# Controller-Sheet.net
KiCad netlist of a schematic drawn in Altium Designer
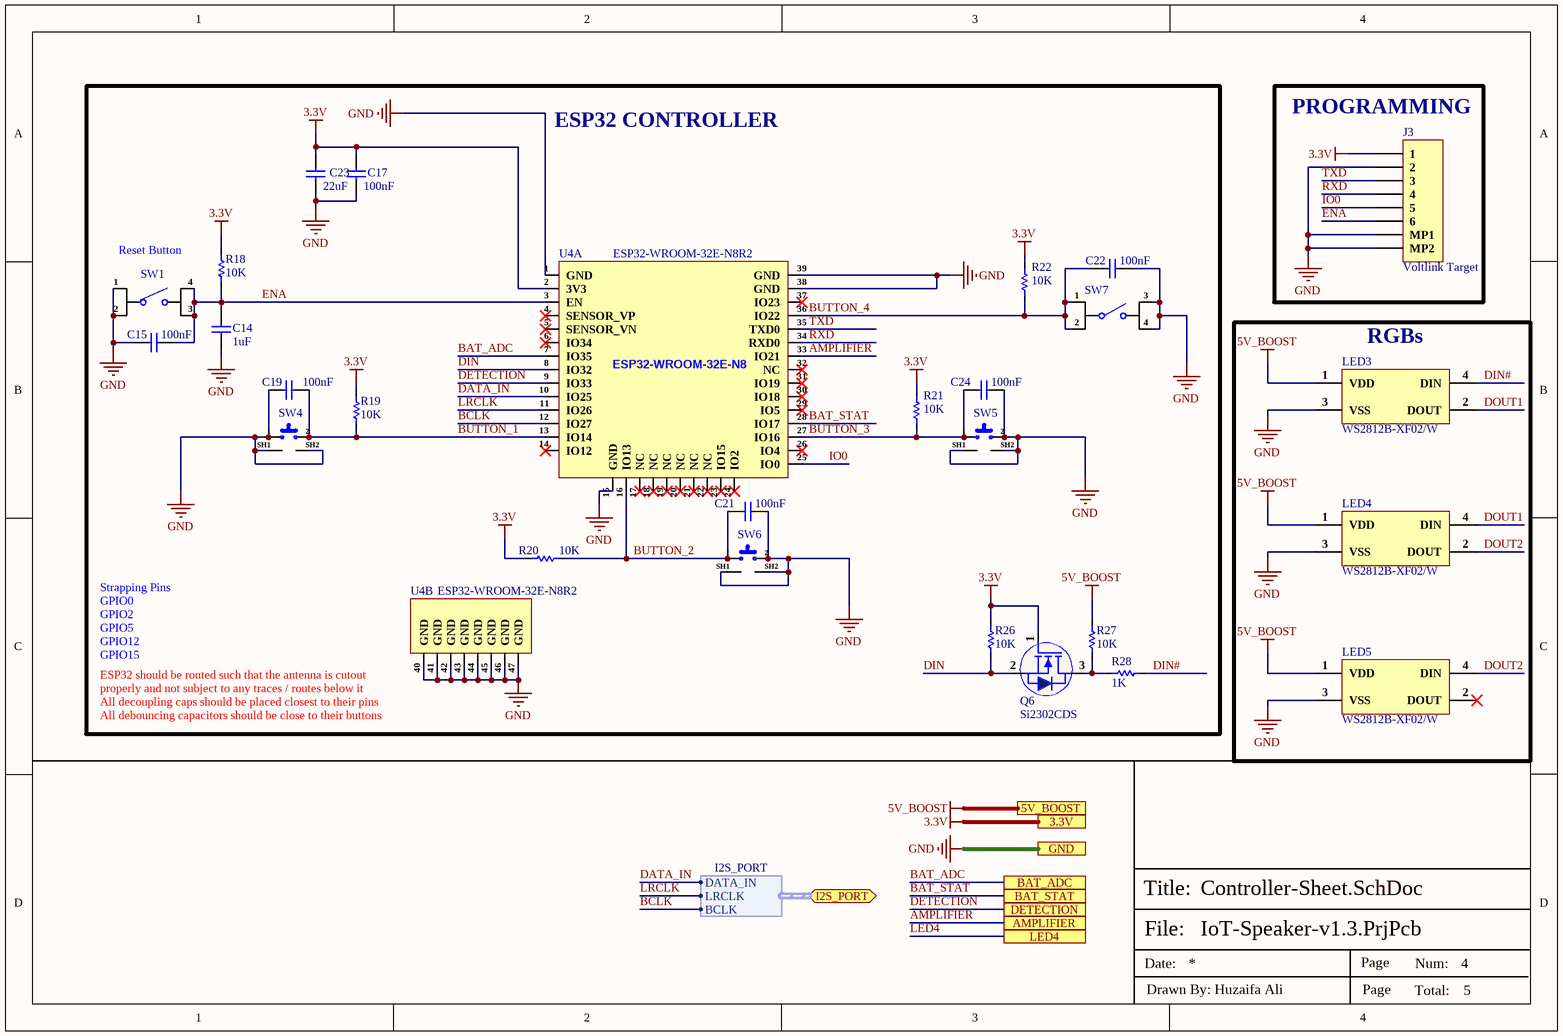
[diagram p0: Controller-Sheet.SchDoc]

(export (version "E")
  (design (tool "Eeschema 10.0.6"))
  (components
    (comp (ref "C14")
      (value "1uF")
      (footprint "Cap-0603")
      (description "CAP CER 1UF 25V X5R 0603")
      (fields
        (field (name "MANUFACTURER") "Yageo")
        (field (name "MANUFACTURER PART NUMBER") "CC0603KRX5R8BB105")
      )
      (libsource (lib "eSpark_centralized_Library(2022)") (part "CC0603KRX5R8BB105"))
    )
    (comp (ref "C15")
      (value "100nF")
      (footprint "Cap-0402")
      (description "CAP CER 0.1UF 25V X5R 0402")
      (fields
        (field (name "MANUFACTURER") "Yageo")
        (field (name "MANUFACTURER PART NUMBER") "CC0402KRX5R8BB104")
      )
      (libsource (lib "eSpark_centralized_Library(2022)") (part "CC0402KRX5R8BB104"))
    )
    (comp (ref "C17")
      (value "100nF")
      (footprint "Cap-0402")
      (description "CAP CER 0.1UF 25V X5R 0402")
      (fields
        (field (name "MANUFACTURER") "Yageo")
        (field (name "MANUFACTURER PART NUMBER") "CC0402KRX5R8BB104")
      )
      (libsource (lib "eSpark_centralized_Library(2022)") (part "CC0402KRX5R8BB104"))
    )
    (comp (ref "C19")
      (value "100nF")
      (footprint "Cap-0402")
      (description "CAP CER 0.1UF 25V X5R 0402")
      (fields
        (field (name "MANUFACTURER") "Yageo")
        (field (name "MANUFACTURER PART NUMBER") "CC0402KRX5R8BB104")
      )
      (libsource (lib "eSpark_centralized_Library(2022)") (part "CC0402KRX5R8BB104"))
    )
    (comp (ref "C21")
      (value "100nF")
      (footprint "Cap-0402")
      (description "CAP CER 0.1UF 25V X5R 0402")
      (fields
        (field (name "MANUFACTURER") "Yageo")
        (field (name "MANUFACTURER PART NUMBER") "CC0402KRX5R8BB104")
      )
      (libsource (lib "eSpark_centralized_Library(2022)") (part "CC0402KRX5R8BB104"))
    )
    (comp (ref "C22")
      (value "100nF")
      (footprint "Cap-0402")
      (description "CAP CER 0.1UF 25V X5R 0402")
      (fields
        (field (name "MANUFACTURER") "Yageo")
        (field (name "MANUFACTURER PART NUMBER") "CC0402KRX5R8BB104")
      )
      (libsource (lib "eSpark_centralized_Library(2022)") (part "CC0402KRX5R8BB104"))
    )
    (comp (ref "C23")
      (value "22uF")
      (footprint "Cap-0603")
      (description "CAP CER 22UF 10V X5R 0603")
      (fields
        (field (name "MANUFACTURER") "Yageo")
        (field (name "MANUFACTURER PART NUMBER") "CC0603MRX5R6BB226")
      )
      (libsource (lib "eSpark_centralized_Library(2022)") (part "CC0603MRX5R6BB226"))
    )
    (comp (ref "C24")
      (value "100nF")
      (footprint "Cap-0402")
      (description "CAP CER 0.1UF 25V X5R 0402")
      (fields
        (field (name "MANUFACTURER") "Yageo")
        (field (name "MANUFACTURER PART NUMBER") "CC0402KRX5R8BB104")
      )
      (libsource (lib "eSpark_centralized_Library(2022)") (part "CC0402KRX5R8BB104"))
    )
    (comp (ref "J3")
      (value "Voltlink Target")
      (footprint "Voltlink Target")
      (description "1x6P SH 1 1mm 6 SMD,P=1mm Wire To Board / Wire To Wire Connector ROHS")
      (fields (field (name "MANUFACTURER") "BOOMELE") (field (name "MANUFACTURER PART NUMBER") "C145963"))
      (libsource (lib "eSpark_centralized_Library(2022)") (part "C145963"))
    )
    (comp (ref "LED3")
      (value "WS2812B-XF02/W")
      (footprint "WS2812B-XF02/W")
      (description "SMD5050 Light Emitting Diodes (LED) ROHS")
      (fields (field (name "MANUFACTURER") "Worldsemi") (field (name "LCSC PART NUMBER") "C4154882"))
      (libsource (lib "eSpark_centralized_Library(2022)") (part "WS2812B-XF02/W"))
    )
    (comp (ref "LED4")
      (value "WS2812B-XF02/W")
      (footprint "WS2812B-XF02/W")
      (description "SMD5050 Light Emitting Diodes (LED) ROHS")
      (fields (field (name "MANUFACTURER") "Worldsemi") (field (name "LCSC PART NUMBER") "C4154882"))
      (libsource (lib "eSpark_centralized_Library(2022)") (part "WS2812B-XF02/W"))
    )
    (comp (ref "LED5")
      (value "WS2812B-XF02/W")
      (footprint "WS2812B-XF02/W")
      (description "SMD5050 Light Emitting Diodes (LED) ROHS")
      (fields (field (name "MANUFACTURER") "Worldsemi") (field (name "LCSC PART NUMBER") "C4154882"))
      (libsource (lib "eSpark_centralized_Library(2022)") (part "WS2812B-XF02/W"))
    )
    (comp (ref "Q6")
      (value "Si2302CDS")
      (footprint "Sot-23")
      (description "N-CHANNEL 20-V (D-S) MOSFET")
      (fields
        (field (name "MANUFACTURER") "TECH PUBLIC")
        (field (name "MANUFACTURER PART NUMBER") "SI2302CDS")
      )
      (libsource (lib "eSpark_centralized_Library(2022)") (part "Si2302CDS"))
    )
    (comp (ref "R18")
      (value "10K")
      (footprint "Res-0603")
      (description "RES SMD 10K Ohm 1% 1/10W 0603")
      (fields
        (field (name "MANUFACTURER") "Yageo")
        (field (name "MANUFACTURER PART NUMBER") "RC0603FR-0710KL")
      )
      (libsource (lib "eSpark_centralized_Library(2022)") (part "RC0603FR-0710KL"))
    )
    (comp (ref "R19")
      (value "10K")
      (footprint "Res-0603")
      (description "RES SMD 10K Ohm 1% 1/10W 0603")
      (fields
        (field (name "MANUFACTURER") "Yageo")
        (field (name "MANUFACTURER PART NUMBER") "RC0603FR-0710KL")
      )
      (libsource (lib "eSpark_centralized_Library(2022)") (part "RC0603FR-0710KL"))
    )
    (comp (ref "R20")
      (value "10K")
      (footprint "Res-0603")
      (description "RES SMD 10K Ohm 1% 1/10W 0603")
      (fields
        (field (name "MANUFACTURER") "Yageo")
        (field (name "MANUFACTURER PART NUMBER") "RC0603FR-0710KL")
      )
      (libsource (lib "eSpark_centralized_Library(2022)") (part "RC0603FR-0710KL"))
    )
    (comp (ref "R21")
      (value "10K")
      (footprint "Res-0603")
      (description "RES SMD 10K Ohm 1% 1/10W 0603")
      (fields
        (field (name "MANUFACTURER") "Yageo")
        (field (name "MANUFACTURER PART NUMBER") "RC0603FR-0710KL")
      )
      (libsource (lib "eSpark_centralized_Library(2022)") (part "RC0603FR-0710KL"))
    )
    (comp (ref "R22")
      (value "10K")
      (footprint "Res-0603")
      (description "RES SMD 10K Ohm 1% 1/10W 0603")
      (fields
        (field (name "MANUFACTURER") "Yageo")
        (field (name "MANUFACTURER PART NUMBER") "RC0603FR-0710KL")
      )
      (libsource (lib "eSpark_centralized_Library(2022)") (part "RC0603FR-0710KL"))
    )
    (comp (ref "R26")
      (value "10K")
      (footprint "Res-0402")
      (description "RES 10K OHM 1% 1/16W 0402")
      (fields
        (field (name "MANUFACTURER") "Yageo")
        (field (name "MANUFACTURER PART NUMBER") "RC0402FR-0710KL")
      )
      (libsource (lib "eSpark_centralized_Library(2022)") (part "RC0402FR-0710KL"))
    )
    (comp (ref "R27")
      (value "10K")
      (footprint "Res-0402")
      (description "RES 10K OHM 1% 1/16W 0402")
      (fields
        (field (name "MANUFACTURER") "Yageo")
        (field (name "MANUFACTURER PART NUMBER") "RC0402FR-0710KL")
      )
      (libsource (lib "eSpark_centralized_Library(2022)") (part "RC0402FR-0710KL"))
    )
    (comp (ref "R28")
      (value "1K")
      (footprint "Res-0603")
      (description "RES SMD 1K OHM 1% 1/10W 0603")
      (fields
        (field (name "MANUFACTURER") "Yageo")
        (field (name "MANUFACTURER PART NUMBER") "RC0603FR-071KL")
      )
      (libsource (lib "eSpark_centralized_Library(2022)") (part "RC0603FR-071KL"))
    )
    (comp (ref "SW1")
      (value "TS-1109S-C-B")
      (footprint "TS-1109S-C-B")
      (fields (field (name "MANUFACTURER") "XKB Connectivity") (field (name "LCSC PART NUMBER") "C381037"))
      (libsource (lib "eSpark_centralized_Library(2022)") (part "TS-1109S-C-B"))
    )
    (comp (ref "SW4")
      (value "TS-1087E-B3D2")
      (footprint "TS-1087E-B3D2")
      (description "Plugin-4P,7.7x3.5mm Tactile Switches ROHS")
      (fields (field (name "MANUFACTURER") "Yuandi") (field (name "LCSC PART NUMBER") "C541963"))
      (libsource (lib "eSpark Libraries") (part "TS-1087E-B3D2"))
    )
    (comp (ref "SW5")
      (value "TS-1087E-B3D2")
      (footprint "TS-1087E-B3D2")
      (description "Plugin-4P,7.7x3.5mm Tactile Switches ROHS")
      (fields (field (name "MANUFACTURER") "Yuandi") (field (name "LCSC PART NUMBER") "C541963"))
      (libsource (lib "eSpark Libraries") (part "TS-1087E-B3D2"))
    )
    (comp (ref "SW6")
      (value "TS-1087E-B3D2")
      (footprint "TS-1087E-B3D2")
      (description "Plugin-4P,7.7x3.5mm Tactile Switches ROHS")
      (fields (field (name "MANUFACTURER") "Yuandi") (field (name "LCSC PART NUMBER") "C541963"))
      (libsource (lib "eSpark Libraries") (part "TS-1087E-B3D2"))
    )
    (comp (ref "SW7")
      (value "TS-1109S-B-J")
      (footprint "TS-1109S-B-J_")
      (fields (field (name "MANUFACTURER") "XKB Connectivity") (field (name "LCSC PART NUMBER") "C480323"))
      (libsource (lib "eSpark_centralized_Library(2022)") (part "TS-1109S-B-J"))
    )
    (comp (ref "U4")
      (value "ESP32-WROOM-32E-N8R2")
      (footprint "38-SMD Module")
      (description "RF TXRX MODULE BT PCB TRACE SMD")
      (fields (field (name "MANUFACTURER") "Espressif Systems") (field (name "LCSC PART NUMBER") "C5361945"))
      (libsource (lib "eSpark Libraries") (part "ESP32-WROOM-32E-N8R2"))
    )
  )
  (nets
    (net (code "2") (name "/AMPLIFIER") (class "Default")
      (node (ref "U4") (pin "33") (pinfunction "IO21_33") (pintype "passive"))
    )
    (net (code "3") (name "/BAT_ADC") (class "Default")
      (node (ref "U4") (pin "7") (pinfunction "IO35_7") (pintype "passive"))
    )
    (net (code "4") (name "/BAT_STAT") (class "Default")
      (node (ref "U4") (pin "28") (pinfunction "IO17_28") (pintype "passive"))
    )
    (net (code "5") (name "/BCLK") (class "Default")
      (node (ref "U4") (pin "12") (pinfunction "IO27_12") (pintype "passive"))
    )
    (net (code "6") (name "/BUTTON_1") (class "Default")
      (node (ref "C19") (pin "1") (pinfunction "1_1") (pintype "passive"))
      (node (ref "R19") (pin "1") (pinfunction "1_1") (pintype "passive"))
      (node (ref "SW4") (pin "2") (pinfunction "2_2") (pintype "passive"))
      (node (ref "U4") (pin "13") (pinfunction "IO14_13") (pintype "passive"))
    )
    (net (code "7") (name "/BUTTON_2") (class "Default")
      (node (ref "C21") (pin "1") (pinfunction "1_1") (pintype "passive"))
      (node (ref "R20") (pin "1") (pinfunction "1_1") (pintype "passive"))
      (node (ref "SW6") (pin "1") (pinfunction "1_1") (pintype "passive"))
      (node (ref "U4") (pin "16") (pinfunction "IO13_16") (pintype "passive"))
    )
    (net (code "8") (name "/BUTTON_3") (class "Default")
      (node (ref "C24") (pin "1") (pinfunction "1_1") (pintype "passive"))
      (node (ref "R21") (pin "1") (pinfunction "1_1") (pintype "passive"))
      (node (ref "SW5") (pin "1") (pinfunction "1_1") (pintype "passive"))
      (node (ref "U4") (pin "27") (pinfunction "IO16_27") (pintype "passive"))
    )
    (net (code "9") (name "/BUTTON_4") (class "Default")
      (node (ref "C22") (pin "1") (pinfunction "1_1") (pintype "passive"))
      (node (ref "R22") (pin "1") (pinfunction "1_1") (pintype "passive"))
      (node (ref "SW7") (pin "1") (pinfunction "1_1") (pintype "passive"))
      (node (ref "SW7") (pin "2") (pinfunction "2_2") (pintype "passive"))
      (node (ref "U4") (pin "36") (pinfunction "IO22_36") (pintype "passive"))
    )
    (net (code "10") (name "/DATA_IN") (class "Default")
      (node (ref "U4") (pin "10") (pinfunction "IO25_10") (pintype "passive"))
    )
    (net (code "11") (name "/DETECTION") (class "Default")
      (node (ref "U4") (pin "9") (pinfunction "IO33_9") (pintype "passive"))
    )
    (net (code "12") (name "/DIN") (class "Default")
      (node (ref "Q6") (pin "2") (pinfunction "S_2") (pintype "passive"))
      (node (ref "R26") (pin "2") (pinfunction "2_2") (pintype "passive"))
      (node (ref "U4") (pin "8") (pinfunction "IO32_8") (pintype "passive"))
    )
    (net (code "13") (name "/DIN#") (class "Default")
      (node (ref "LED3") (pin "4") (pinfunction "DIN_4") (pintype "passive"))
      (node (ref "R28") (pin "2") (pinfunction "2_2") (pintype "passive"))
    )
    (net (code "14") (name "/DOUT1") (class "Default")
      (node (ref "LED3") (pin "2") (pinfunction "DOUT_2") (pintype "passive"))
      (node (ref "LED4") (pin "4") (pinfunction "DIN_4") (pintype "passive"))
    )
    (net (code "15") (name "/DOUT2") (class "Default")
      (node (ref "LED4") (pin "2") (pinfunction "DOUT_2") (pintype "passive"))
      (node (ref "LED5") (pin "4") (pinfunction "DIN_4") (pintype "passive"))
    )
    (net (code "16") (name "/ENA") (class "Default")
      (node (ref "C14") (pin "2") (pinfunction "2_2") (pintype "passive"))
      (node (ref "C15") (pin "2") (pinfunction "2_2") (pintype "passive"))
      (node (ref "J3") (pin "6") (pinfunction "6_6") (pintype "passive"))
      (node (ref "R18") (pin "1") (pinfunction "1_1") (pintype "passive"))
      (node (ref "SW1") (pin "3") (pinfunction "3_3") (pintype "passive"))
      (node (ref "SW1") (pin "4") (pinfunction "4_4") (pintype "passive"))
      (node (ref "U4") (pin "3") (pinfunction "EN_3") (pintype "passive"))
    )
    (net (code "17") (name "/IO0") (class "Default")
      (node (ref "J3") (pin "5") (pinfunction "5_5") (pintype "passive"))
      (node (ref "U4") (pin "25") (pinfunction "IO0_25") (pintype "passive"))
    )
    (net (code "19") (name "/LRCLK") (class "Default")
      (node (ref "U4") (pin "11") (pinfunction "IO26_11") (pintype "passive"))
    )
    (net (code "20") (name "/RXD") (class "Default")
      (node (ref "J3") (pin "4") (pinfunction "4_4") (pintype "passive"))
      (node (ref "U4") (pin "34") (pinfunction "RXD0_34") (pintype "passive"))
    )
    (net (code "21") (name "/TXD") (class "Default")
      (node (ref "J3") (pin "3") (pinfunction "3_3") (pintype "passive"))
      (node (ref "U4") (pin "35") (pinfunction "TXD0_35") (pintype "passive"))
    )
    (net (code "23") (name "3.3V") (class "Default")
      (node (ref "C17") (pin "2") (pinfunction "2_2") (pintype "passive"))
      (node (ref "C23") (pin "2") (pinfunction "2_2") (pintype "passive"))
      (node (ref "J3") (pin "1") (pinfunction "1_1") (pintype "passive"))
      (node (ref "Q6") (pin "1") (pinfunction "G_1") (pintype "passive"))
      (node (ref "R18") (pin "2") (pinfunction "2_2") (pintype "passive"))
      (node (ref "R19") (pin "2") (pinfunction "2_2") (pintype "passive"))
      (node (ref "R20") (pin "2") (pinfunction "2_2") (pintype "passive"))
      (node (ref "R21") (pin "2") (pinfunction "2_2") (pintype "passive"))
      (node (ref "R22") (pin "2") (pinfunction "2_2") (pintype "passive"))
      (node (ref "R26") (pin "1") (pinfunction "1_1") (pintype "passive"))
      (node (ref "U4") (pin "2") (pinfunction "3V3_2") (pintype "passive"))
    )
    (net (code "24") (name "5V_BOOST") (class "Default")
      (node (ref "LED3") (pin "1") (pinfunction "VDD_1") (pintype "passive"))
      (node (ref "LED4") (pin "1") (pinfunction "VDD_1") (pintype "passive"))
      (node (ref "LED5") (pin "1") (pinfunction "VDD_1") (pintype "passive"))
      (node (ref "R27") (pin "1") (pinfunction "1_1") (pintype "passive"))
    )
    (net (code "25") (name "GND") (class "Default")
      (node (ref "C14") (pin "1") (pinfunction "1_1") (pintype "passive"))
      (node (ref "C15") (pin "1") (pinfunction "1_1") (pintype "passive"))
      (node (ref "C17") (pin "1") (pinfunction "1_1") (pintype "passive"))
      (node (ref "C19") (pin "2") (pinfunction "2_2") (pintype "passive"))
      (node (ref "C21") (pin "2") (pinfunction "2_2") (pintype "passive"))
      (node (ref "C22") (pin "2") (pinfunction "2_2") (pintype "passive"))
      (node (ref "C23") (pin "1") (pinfunction "1_1") (pintype "passive"))
      (node (ref "C24") (pin "2") (pinfunction "2_2") (pintype "passive"))
      (node (ref "J3") (pin "2") (pinfunction "2_2") (pintype "passive"))
      (node (ref "J3") (pin "MP1") (pinfunction "MP1_MP1") (pintype "passive"))
      (node (ref "J3") (pin "MP2") (pinfunction "MP2_MP2") (pintype "passive"))
      (node (ref "LED3") (pin "3") (pinfunction "VSS_3") (pintype "passive"))
      (node (ref "LED4") (pin "3") (pinfunction "VSS_3") (pintype "passive"))
      (node (ref "LED5") (pin "3") (pinfunction "VSS_3") (pintype "passive"))
      (node (ref "SW1") (pin "1") (pinfunction "1_1") (pintype "passive"))
      (node (ref "SW1") (pin "2") (pinfunction "2_2") (pintype "passive"))
      (node (ref "SW4") (pin "1") (pinfunction "1_1") (pintype "passive"))
      (node (ref "SW4") (pin "SH1") (pinfunction "SH1_SH1") (pintype "passive"))
      (node (ref "SW4") (pin "SH2") (pinfunction "SH2_SH2") (pintype "passive"))
      (node (ref "SW5") (pin "2") (pinfunction "2_2") (pintype "passive"))
      (node (ref "SW5") (pin "SH1") (pinfunction "SH1_SH1") (pintype "passive"))
      (node (ref "SW5") (pin "SH2") (pinfunction "SH2_SH2") (pintype "passive"))
      (node (ref "SW6") (pin "2") (pinfunction "2_2") (pintype "passive"))
      (node (ref "SW6") (pin "SH1") (pinfunction "SH1_SH1") (pintype "passive"))
      (node (ref "SW6") (pin "SH2") (pinfunction "SH2_SH2") (pintype "passive"))
      (node (ref "SW7") (pin "3") (pinfunction "3_3") (pintype "passive"))
      (node (ref "SW7") (pin "4") (pinfunction "4_4") (pintype "passive"))
      (node (ref "U4") (pin "1") (pinfunction "GND_1") (pintype "passive"))
      (node (ref "U4") (pin "15") (pinfunction "GND_15") (pintype "passive"))
      (node (ref "U4") (pin "38") (pinfunction "GND_38") (pintype "passive"))
      (node (ref "U4") (pin "39") (pinfunction "GND_39") (pintype "passive"))
      (node (ref "U4") (pin "40") (pinfunction "GND_40") (pintype "passive"))
      (node (ref "U4") (pin "41") (pinfunction "GND_41") (pintype "passive"))
      (node (ref "U4") (pin "42") (pinfunction "GND_42") (pintype "passive"))
      (node (ref "U4") (pin "43") (pinfunction "GND_43") (pintype "passive"))
      (node (ref "U4") (pin "44") (pinfunction "GND_44") (pintype "passive"))
      (node (ref "U4") (pin "45") (pinfunction "GND_45") (pintype "passive"))
      (node (ref "U4") (pin "46") (pinfunction "GND_46") (pintype "passive"))
      (node (ref "U4") (pin "47") (pinfunction "GND_47") (pintype "passive"))
    )
    (net (code "26") (name "Net-(Q6-D)") (class "Default")
      (node (ref "Q6") (pin "3") (pinfunction "D_3") (pintype "passive"))
      (node (ref "R27") (pin "2") (pinfunction "2_2") (pintype "passive"))
      (node (ref "R28") (pin "1") (pinfunction "1_1") (pintype "passive"))
    )
    (net (code "27") (name "unconnected-(LED5-DOUT-Pad2)") (class "Default")
      (node (ref "LED5") (pin "2") (pinfunction "DOUT_2") (pintype "passive+no_connect"))
    )
    (net (code "28") (name "unconnected-(U4A-IO2-Pad24)") (class "Default")
      (node (ref "U4") (pin "24") (pinfunction "IO2_24") (pintype "passive+no_connect"))
    )
    (net (code "29") (name "unconnected-(U4A-IO4-Pad26)") (class "Default")
      (node (ref "U4") (pin "26") (pinfunction "IO4_26") (pintype "passive+no_connect"))
    )
    (net (code "30") (name "unconnected-(U4A-IO5-Pad29)") (class "Default")
      (node (ref "U4") (pin "29") (pinfunction "IO5_29") (pintype "passive+no_connect"))
    )
    (net (code "31") (name "unconnected-(U4A-IO12-Pad14)") (class "Default")
      (node (ref "U4") (pin "14") (pinfunction "IO12_14") (pintype "passive+no_connect"))
    )
    (net (code "32") (name "unconnected-(U4A-IO15-Pad23)") (class "Default")
      (node (ref "U4") (pin "23") (pinfunction "IO15_23") (pintype "passive+no_connect"))
    )
    (net (code "33") (name "unconnected-(U4A-IO18-Pad30)") (class "Default")
      (node (ref "U4") (pin "30") (pinfunction "IO18_30") (pintype "passive+no_connect"))
    )
    (net (code "34") (name "unconnected-(U4A-IO19-Pad31)") (class "Default")
      (node (ref "U4") (pin "31") (pinfunction "IO19_31") (pintype "passive+no_connect"))
    )
    (net (code "35") (name "unconnected-(U4A-IO23-Pad37)") (class "Default")
      (node (ref "U4") (pin "37") (pinfunction "IO23_37") (pintype "passive+no_connect"))
    )
    (net (code "36") (name "unconnected-(U4A-IO34-Pad6)") (class "Default")
      (node (ref "U4") (pin "6") (pinfunction "IO34_6") (pintype "passive+no_connect"))
    )
    (net (code "37") (name "unconnected-(U4A-NC-Pad17)") (class "Default")
      (node (ref "U4") (pin "17") (pinfunction "NC_17") (pintype "passive+no_connect"))
    )
    (net (code "38") (name "unconnected-(U4A-NC-Pad18)") (class "Default")
      (node (ref "U4") (pin "18") (pinfunction "NC_18") (pintype "passive+no_connect"))
    )
    (net (code "39") (name "unconnected-(U4A-NC-Pad19)") (class "Default")
      (node (ref "U4") (pin "19") (pinfunction "NC_19") (pintype "passive+no_connect"))
    )
    (net (code "40") (name "unconnected-(U4A-NC-Pad20)") (class "Default")
      (node (ref "U4") (pin "20") (pinfunction "NC_20") (pintype "passive+no_connect"))
    )
    (net (code "41") (name "unconnected-(U4A-NC-Pad21)") (class "Default")
      (node (ref "U4") (pin "21") (pinfunction "NC_21") (pintype "passive+no_connect"))
    )
    (net (code "42") (name "unconnected-(U4A-NC-Pad22)") (class "Default")
      (node (ref "U4") (pin "22") (pinfunction "NC_22") (pintype "passive+no_connect"))
    )
    (net (code "43") (name "unconnected-(U4A-NC-Pad32)") (class "Default")
      (node (ref "U4") (pin "32") (pinfunction "NC_32") (pintype "passive+no_connect"))
    )
    (net (code "44") (name "unconnected-(U4A-SENSOR_VN-Pad5)") (class "Default")
      (node (ref "U4") (pin "5") (pinfunction "SENSOR_VN_5") (pintype "passive+no_connect"))
    )
    (net (code "45") (name "unconnected-(U4A-SENSOR_VP-Pad4)") (class "Default")
      (node (ref "U4") (pin "4") (pinfunction "SENSOR_VP_4") (pintype "passive+no_connect"))
    )
  )
)
